# SIM7000_Shield_ES.net
KiCad netlist of a schematic drawn in EAGLE
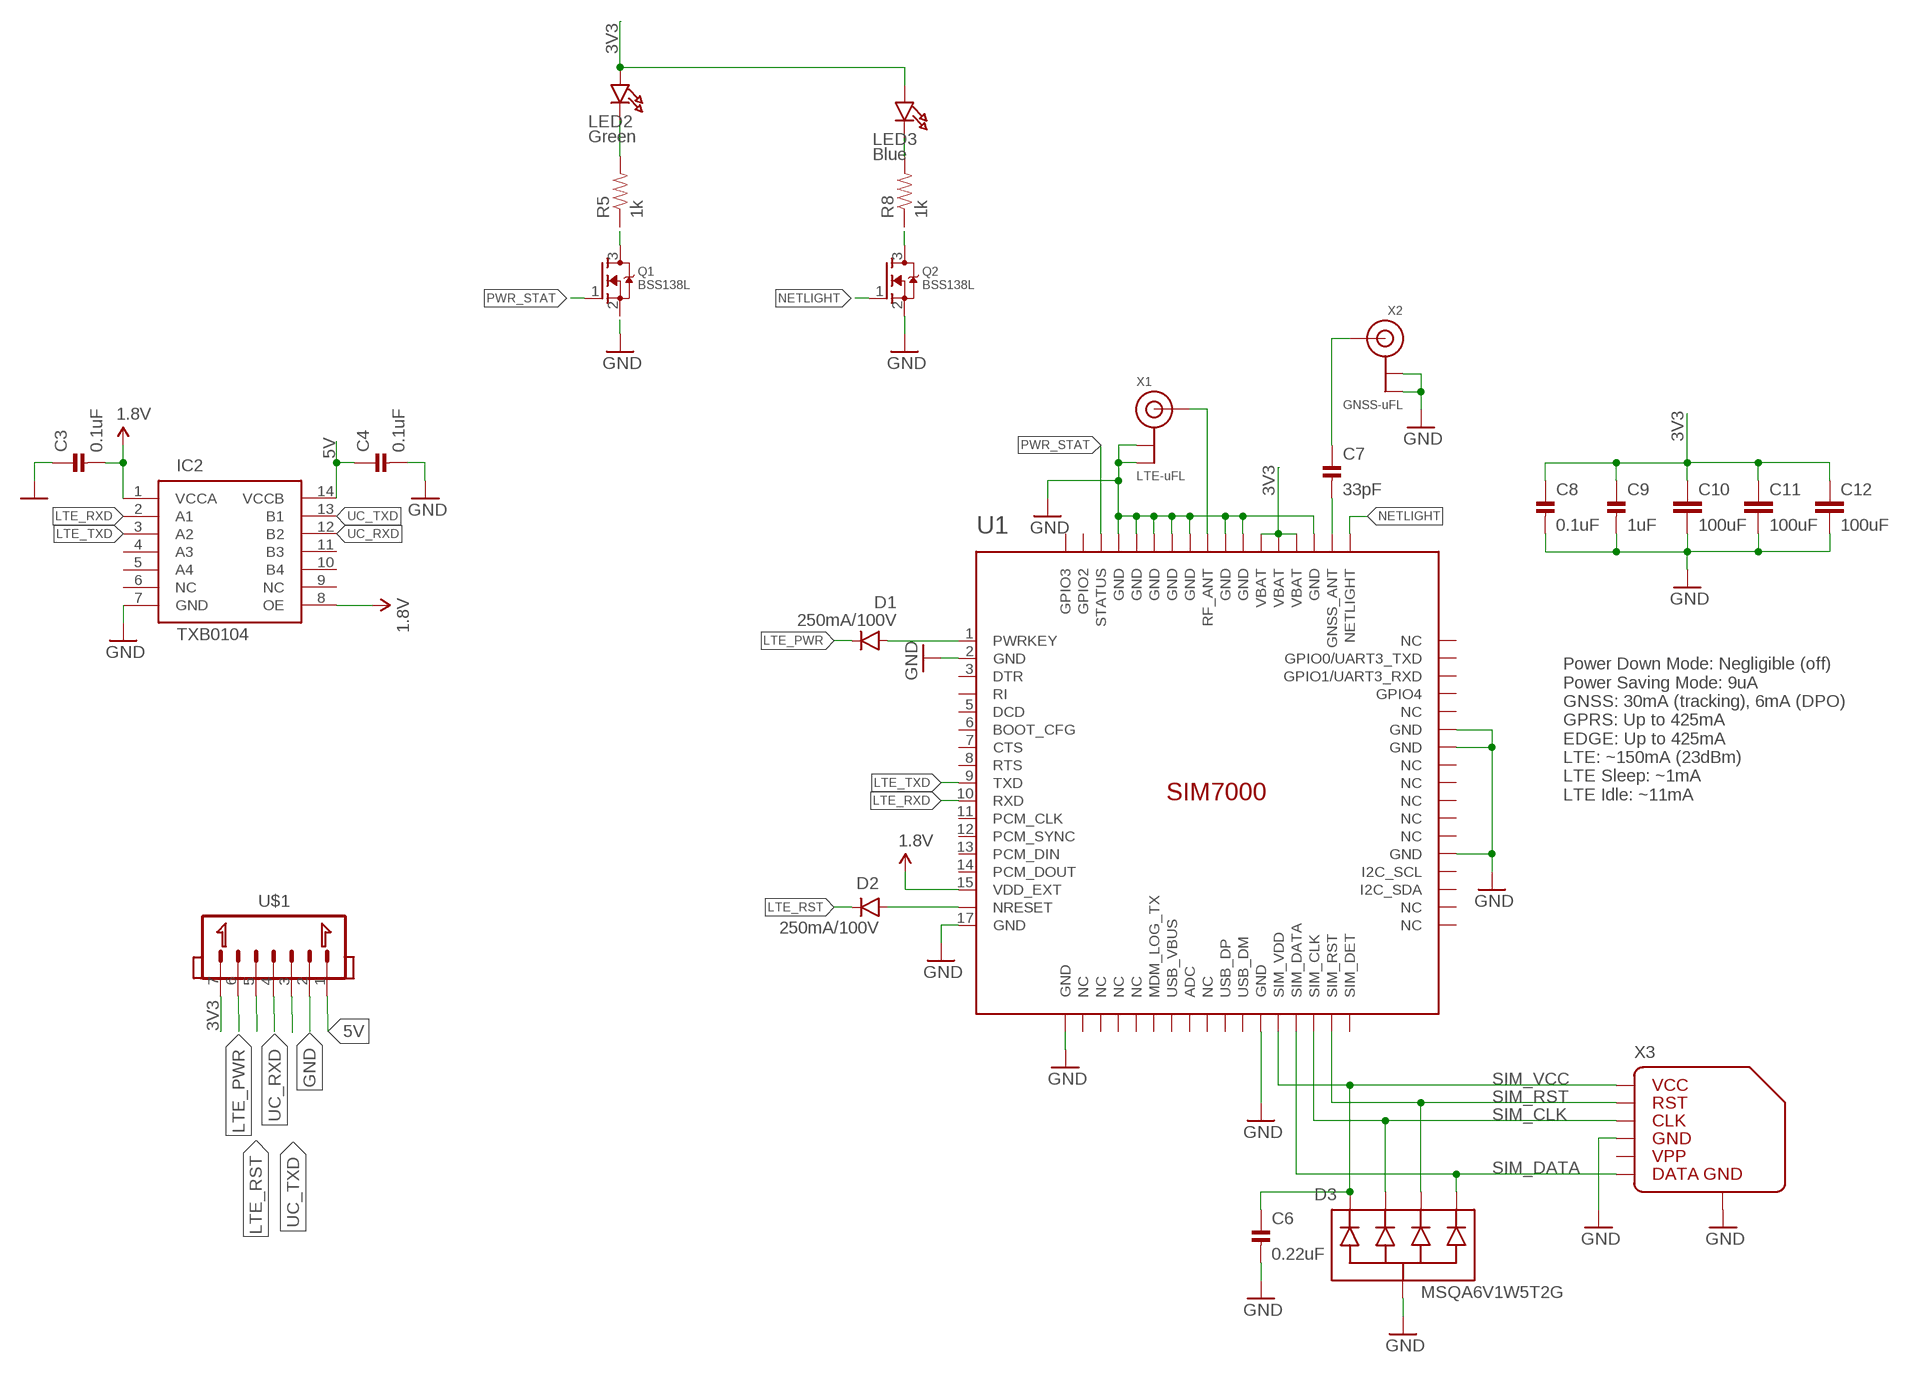
[diagram p0: schematic, sheet 1]

(export (version "E")
  (design (tool "Eeschema 10.0.6"))
  (components
    (comp (ref "C3")
      (value "0.1uF")
      (footprint "eagle-import:CAP_0603")
      (libsource (lib "eagle-import") (part "CAP_CERAMIC_0603"))
    )
    (comp (ref "C4")
      (value "0.1uF")
      (footprint "eagle-import:CAP_0603")
      (libsource (lib "eagle-import") (part "CAP_CERAMIC_0603"))
    )
    (comp (ref "C6")
      (value "0.22uF")
      (footprint "eagle-import:CAP_0603")
      (libsource (lib "eagle-import") (part "CAP_CERAMIC_0603"))
    )
    (comp (ref "C7")
      (value "33pF")
      (footprint "eagle-import:CAP_0603")
      (libsource (lib "eagle-import") (part "CAP_CERAMIC_0603"))
    )
    (comp (ref "C8")
      (value "0.1uF")
      (footprint "eagle-import:CAP_0603")
      (libsource (lib "eagle-import") (part "CAP_CERAMIC_0603"))
    )
    (comp (ref "C9")
      (value "1uF")
      (footprint "eagle-import:CAP_0603")
      (libsource (lib "eagle-import") (part "CAP_CERAMIC_0603"))
    )
    (comp (ref "C10")
      (value "100uF")
      (footprint "eagle-import:1210")
      (libsource (lib "eagle-import") (part "CAPMARKED-1210"))
    )
    (comp (ref "C11")
      (value "100uF")
      (footprint "eagle-import:1210")
      (libsource (lib "eagle-import") (part "CAPMARKED-1210"))
    )
    (comp (ref "C12")
      (value "100uF")
      (footprint "eagle-import:1210")
      (libsource (lib "eagle-import") (part "CAPMARKED-1210"))
    )
    (comp (ref "D1")
      (value "250mA/100V")
      (footprint "eagle-import:SOD-323")
      (libsource (lib "eagle-import") (part "DIODESOD323"))
    )
    (comp (ref "D2")
      (value "250mA/100V")
      (footprint "eagle-import:SOD-323")
      (libsource (lib "eagle-import") (part "DIODESOD323"))
    )
    (comp (ref "D3")
      (value "MSQA6V1W5T2G")
      (footprint "eagle-import:SOT-353")
      (libsource (lib "eagle-import") (part "TVS-DIODE-ARRAY-4X"))
    )
    (comp (ref "IC2")
      (value "TXB0104")
      (footprint "eagle-import:TSSOP-14")
      (libsource (lib "eagle-import") (part "LEVEL_SHIFTER_TXB0104"))
    )
    (comp (ref "LED2")
      (value "Green")
      (footprint "eagle-import:MICROBUILDER_CHIPLED_0603")
      (libsource (lib "eagle-import") (part "LED0603"))
    )
    (comp (ref "LED3")
      (value "Blue")
      (footprint "eagle-import:MICROBUILDER_CHIPLED_0603")
      (libsource (lib "eagle-import") (part "LED0603"))
    )
    (comp (ref "Q1")
      (value "BSS138L")
      (footprint "eagle-import:SOT23-3")
      (libsource (lib "eagle-import") (part "MOSFET-NGENERIC"))
    )
    (comp (ref "Q2")
      (value "BSS138L")
      (footprint "eagle-import:SOT23-3")
      (libsource (lib "eagle-import") (part "MOSFET-NGENERIC"))
    )
    (comp (ref "R5")
      (value "1k")
      (footprint "eagle-import:0603")
      (libsource (lib "eagle-import") (part "RESISTOR0603"))
    )
    (comp (ref "R8")
      (value "1k")
      (footprint "eagle-import:0603")
      (libsource (lib "eagle-import") (part "RESISTOR0603"))
    )
    (comp (ref "U$1")
      (value "JST_1.25_7P")
      (footprint "eagle-import:JST1.25_7P")
      (libsource (lib "eagle-import") (part "JST_1.25_7P"))
    )
    (comp (ref "U1")
      (value "SIM7000")
      (footprint "eagle-import:SIM7000")
      (libsource (lib "eagle-import") (part "SIM7000"))
    )
    (comp (ref "X1")
      (value "LTE-uFL")
      (footprint "eagle-import:U.FL")
      (libsource (lib "eagle-import") (part "ANTENNA_U.FL"))
    )
    (comp (ref "X2")
      (value "GNSS-uFL")
      (footprint "eagle-import:U.FL")
      (libsource (lib "eagle-import") (part "ANTENNA_U.FL"))
    )
    (comp (ref "X3")
      (value "MICROSIM_SOCKET")
      (footprint "eagle-import:MICROSIM_SOCKET")
      (libsource (lib "eagle-import") (part "MICROSIM_SOCKET"))
    )
  )
  (nets
    (net (code "1") (name "/3V3") (class "Default")
      (node (ref "C10") (pin "1") (pinfunction "1_1") (pintype "passive"))
      (node (ref "C11") (pin "1") (pinfunction "1_1") (pintype "passive"))
      (node (ref "C12") (pin "1") (pinfunction "1_1") (pintype "passive"))
      (node (ref "C8") (pin "1") (pinfunction "1_1") (pintype "passive"))
      (node (ref "C9") (pin "1") (pinfunction "1_1") (pintype "passive"))
      (node (ref "LED2") (pin "A") (pinfunction "A_A") (pintype "passive"))
      (node (ref "LED3") (pin "A") (pinfunction "A_A") (pintype "passive"))
      (node (ref "U$1") (pin "7") (pinfunction "7_7") (pintype "passive"))
      (node (ref "U1") (pin "55") (pinfunction "VBAT_55") (pintype "bidirectional"))
      (node (ref "U1") (pin "56") (pinfunction "VBAT_56") (pintype "bidirectional"))
      (node (ref "U1") (pin "57") (pinfunction "VBAT_57") (pintype "bidirectional"))
    )
    (net (code "2") (name "/SIM_CLK") (class "Default")
      (node (ref "D3") (pin "3") (pinfunction "2_3") (pintype "bidirectional"))
      (node (ref "U1") (pin "32") (pinfunction "SIM_CLK_32") (pintype "bidirectional"))
      (node (ref "X3") (pin "C3") (pinfunction "C3_C3") (pintype "passive"))
    )
    (net (code "3") (name "/SIM_DATA") (class "Default")
      (node (ref "D3") (pin "5") (pinfunction "4_5") (pintype "bidirectional"))
      (node (ref "U1") (pin "31") (pinfunction "SIM_DATA_31") (pintype "bidirectional"))
      (node (ref "X3") (pin "C7") (pinfunction "C7_C7") (pintype "passive"))
    )
    (net (code "4") (name "/SIM_RST") (class "Default")
      (node (ref "D3") (pin "4") (pinfunction "3_4") (pintype "bidirectional"))
      (node (ref "U1") (pin "33") (pinfunction "SIM_RST_33") (pintype "bidirectional"))
      (node (ref "X3") (pin "C2") (pinfunction "C2_C2") (pintype "passive"))
    )
    (net (code "5") (name "/SIM_VCC") (class "Default")
      (node (ref "C6") (pin "1") (pinfunction "1_1") (pintype "passive"))
      (node (ref "D3") (pin "1") (pinfunction "1_1") (pintype "bidirectional"))
      (node (ref "U1") (pin "30") (pinfunction "SIM_VDD_30") (pintype "bidirectional"))
      (node (ref "X3") (pin "C1") (pinfunction "C1_C1") (pintype "power_in"))
    )
    (net (code "6") (name "1.8V") (class "Default")
      (node (ref "C3") (pin "2") (pinfunction "2_2") (pintype "passive"))
      (node (ref "IC2") (pin "1") (pinfunction "VCCA_1") (pintype "power_in"))
      (node (ref "IC2") (pin "8") (pinfunction "OE_8") (pintype "bidirectional"))
      (node (ref "U1") (pin "15") (pinfunction "VDD_EXT_15") (pintype "bidirectional"))
    )
    (net (code "7") (name "5V") (class "Default")
      (node (ref "C4") (pin "1") (pinfunction "1_1") (pintype "passive"))
      (node (ref "IC2") (pin "14") (pinfunction "VCCB_14") (pintype "power_in"))
      (node (ref "U$1") (pin "1") (pinfunction "1_1") (pintype "passive"))
    )
    (net (code "8") (name "GND") (class "Default")
      (node (ref "C10") (pin "2") (pinfunction "2_2") (pintype "passive"))
      (node (ref "C11") (pin "2") (pinfunction "2_2") (pintype "passive"))
      (node (ref "C12") (pin "2") (pinfunction "2_2") (pintype "passive"))
      (node (ref "C3") (pin "1") (pinfunction "1_1") (pintype "passive"))
      (node (ref "C4") (pin "2") (pinfunction "2_2") (pintype "passive"))
      (node (ref "C6") (pin "2") (pinfunction "2_2") (pintype "passive"))
      (node (ref "C8") (pin "2") (pinfunction "2_2") (pintype "passive"))
      (node (ref "C9") (pin "2") (pinfunction "2_2") (pintype "passive"))
      (node (ref "D3") (pin "2") (pinfunction "COM_2") (pintype "bidirectional"))
      (node (ref "IC2") (pin "7") (pinfunction "GND_7") (pintype "power_in"))
      (node (ref "Q1") (pin "2") (pinfunction "S_2") (pintype "bidirectional"))
      (node (ref "Q2") (pin "2") (pinfunction "S_2") (pintype "bidirectional"))
      (node (ref "U$1") (pin "2") (pinfunction "2_2") (pintype "passive"))
      (node (ref "U1") (pin "17") (pinfunction "GND_17") (pintype "bidirectional"))
      (node (ref "U1") (pin "18") (pinfunction "GND_18") (pintype "bidirectional"))
      (node (ref "U1") (pin "2") (pinfunction "GND_2") (pintype "bidirectional"))
      (node (ref "U1") (pin "29") (pinfunction "GND_29") (pintype "bidirectional"))
      (node (ref "U1") (pin "39") (pinfunction "GND_39") (pintype "bidirectional"))
      (node (ref "U1") (pin "45") (pinfunction "GND_45") (pintype "bidirectional"))
      (node (ref "U1") (pin "46") (pinfunction "GND_46") (pintype "bidirectional"))
      (node (ref "U1") (pin "54") (pinfunction "GND_54") (pintype "bidirectional"))
      (node (ref "U1") (pin "58") (pinfunction "GND_58") (pintype "bidirectional"))
      (node (ref "U1") (pin "59") (pinfunction "GND_59") (pintype "bidirectional"))
      (node (ref "U1") (pin "61") (pinfunction "GND_61") (pintype "bidirectional"))
      (node (ref "U1") (pin "62") (pinfunction "GND_62") (pintype "bidirectional"))
      (node (ref "U1") (pin "63") (pinfunction "GND_63") (pintype "bidirectional"))
      (node (ref "U1") (pin "64") (pinfunction "GND_64") (pintype "bidirectional"))
      (node (ref "U1") (pin "65") (pinfunction "GND_65") (pintype "bidirectional"))
      (node (ref "X1") (pin "1") (pinfunction "GND_1") (pintype "passive"))
      (node (ref "X1") (pin "2") (pinfunction "GND_2") (pintype "passive"))
      (node (ref "X2") (pin "1") (pinfunction "GND_1") (pintype "passive"))
      (node (ref "X2") (pin "2") (pinfunction "GND_2") (pintype "passive"))
      (node (ref "X3") (pin "C5") (pinfunction "C5_C5") (pintype "power_in"))
      (node (ref "X3") (pin "GND@1") (pinfunction "GND_GND@1") (pintype "power_in"))
      (node (ref "X3") (pin "GND@10") (pinfunction "GND_GND@10") (pintype "power_in"))
      (node (ref "X3") (pin "GND@2") (pinfunction "GND_GND@2") (pintype "power_in"))
      (node (ref "X3") (pin "GND@3") (pinfunction "GND_GND@3") (pintype "power_in"))
      (node (ref "X3") (pin "GND@4") (pinfunction "GND_GND@4") (pintype "power_in"))
      (node (ref "X3") (pin "GND@5") (pinfunction "GND_GND@5") (pintype "power_in"))
      (node (ref "X3") (pin "GND@6") (pinfunction "GND_GND@6") (pintype "power_in"))
      (node (ref "X3") (pin "GND@7") (pinfunction "GND_GND@7") (pintype "power_in"))
      (node (ref "X3") (pin "GND@8") (pinfunction "GND_GND@8") (pintype "power_in"))
      (node (ref "X3") (pin "GND@9") (pinfunction "GND_GND@9") (pintype "power_in"))
    )
    (net (code "9") (name "LTE_PWR") (class "Default")
      (node (ref "D1") (pin "C") (pinfunction "C_C") (pintype "passive"))
      (node (ref "U$1") (pin "6") (pinfunction "6_6") (pintype "passive"))
    )
    (net (code "10") (name "LTE_RST") (class "Default")
      (node (ref "D2") (pin "C") (pinfunction "C_C") (pintype "passive"))
      (node (ref "U$1") (pin "5") (pinfunction "5_5") (pintype "passive"))
    )
    (net (code "11") (name "LTE_RXD") (class "Default")
      (node (ref "IC2") (pin "2") (pinfunction "A1_2") (pintype "bidirectional"))
      (node (ref "U1") (pin "10") (pinfunction "RXD_10") (pintype "bidirectional"))
    )
    (net (code "12") (name "LTE_TXD") (class "Default")
      (node (ref "IC2") (pin "3") (pinfunction "A2_3") (pintype "bidirectional"))
      (node (ref "U1") (pin "9") (pinfunction "TXD_9") (pintype "bidirectional"))
    )
    (net (code "13") (name "NETLIGHT") (class "Default")
      (node (ref "Q2") (pin "1") (pinfunction "G_1") (pintype "bidirectional"))
      (node (ref "U1") (pin "52") (pinfunction "NETLIGHT_52") (pintype "bidirectional"))
    )
    (net (code "14") (name "Net-(LED2-PadC)") (class "Default")
      (node (ref "LED2") (pin "C") (pinfunction "C_C") (pintype "passive"))
      (node (ref "R5") (pin "2") (pinfunction "2_2") (pintype "passive"))
    )
    (net (code "15") (name "Net-(LED3-PadC)") (class "Default")
      (node (ref "LED3") (pin "C") (pinfunction "C_C") (pintype "passive"))
      (node (ref "R8") (pin "2") (pinfunction "2_2") (pintype "passive"))
    )
    (net (code "16") (name "Net-(Q1-D)") (class "Default")
      (node (ref "Q1") (pin "3") (pinfunction "D_3") (pintype "bidirectional"))
      (node (ref "R5") (pin "1") (pinfunction "1_1") (pintype "passive"))
    )
    (net (code "17") (name "Net-(Q2-D)") (class "Default")
      (node (ref "Q2") (pin "3") (pinfunction "D_3") (pintype "bidirectional"))
      (node (ref "R8") (pin "1") (pinfunction "1_1") (pintype "passive"))
    )
    (net (code "18") (name "Net-(U1-GNSS_ANT)") (class "Default")
      (node (ref "C7") (pin "2") (pinfunction "2_2") (pintype "passive"))
      (node (ref "U1") (pin "53") (pinfunction "GNSS_ANT_53") (pintype "bidirectional"))
    )
    (net (code "19") (name "Net-(U1-NRESET)") (class "Default")
      (node (ref "D2") (pin "A") (pinfunction "A_A") (pintype "passive"))
      (node (ref "U1") (pin "16") (pinfunction "NRESET_16") (pintype "bidirectional"))
    )
    (net (code "20") (name "Net-(U1-PWRKEY)") (class "Default")
      (node (ref "D1") (pin "A") (pinfunction "A_A") (pintype "passive"))
      (node (ref "U1") (pin "1") (pinfunction "PWRKEY_1") (pintype "bidirectional"))
    )
    (net (code "21") (name "Net-(U1-RF_ANT)") (class "Default")
      (node (ref "U1") (pin "60") (pinfunction "RF_ANT_60") (pintype "bidirectional"))
      (node (ref "X1") (pin "3") (pinfunction "SIGNAL_3") (pintype "passive"))
    )
    (net (code "22") (name "Net-(X2-SIGNAL)") (class "Default")
      (node (ref "C7") (pin "1") (pinfunction "1_1") (pintype "passive"))
      (node (ref "X2") (pin "3") (pinfunction "SIGNAL_3") (pintype "passive"))
    )
    (net (code "23") (name "PWR_STAT") (class "Default")
      (node (ref "Q1") (pin "1") (pinfunction "G_1") (pintype "bidirectional"))
      (node (ref "U1") (pin "66") (pinfunction "STATUS_66") (pintype "bidirectional"))
    )
    (net (code "24") (name "UC_RXD") (class "Default")
      (node (ref "IC2") (pin "12") (pinfunction "B2_12") (pintype "bidirectional"))
      (node (ref "U$1") (pin "4") (pinfunction "4_4") (pintype "passive"))
    )
    (net (code "25") (name "UC_TXD") (class "Default")
      (node (ref "IC2") (pin "13") (pinfunction "B1_13") (pintype "bidirectional"))
      (node (ref "U$1") (pin "3") (pinfunction "3_3") (pintype "passive"))
    )
    (net (code "26") (name "unconnected-(IC2-A3-Pad4)") (class "Default")
      (node (ref "IC2") (pin "4") (pinfunction "A3_4") (pintype "bidirectional"))
    )
    (net (code "27") (name "unconnected-(IC2-A4-Pad5)") (class "Default")
      (node (ref "IC2") (pin "5") (pinfunction "A4_5") (pintype "bidirectional"))
    )
    (net (code "28") (name "unconnected-(IC2-B3-Pad11)") (class "Default")
      (node (ref "IC2") (pin "11") (pinfunction "B3_11") (pintype "bidirectional"))
    )
    (net (code "29") (name "unconnected-(IC2-B4-Pad10)") (class "Default")
      (node (ref "IC2") (pin "10") (pinfunction "B4_10") (pintype "bidirectional"))
    )
    (net (code "30") (name "unconnected-(IC2-NC-Pad6)") (class "Default")
      (node (ref "IC2") (pin "6") (pinfunction "NC_6") (pintype "bidirectional"))
    )
    (net (code "31") (name "unconnected-(IC2-NC-Pad9)") (class "Default")
      (node (ref "IC2") (pin "9") (pinfunction "NC_9") (pintype "bidirectional"))
    )
    (net (code "32") (name "unconnected-(U1-ADC-Pad25)") (class "Default")
      (node (ref "U1") (pin "25") (pinfunction "ADC_25") (pintype "bidirectional"))
    )
    (net (code "33") (name "unconnected-(U1-BOOT_CFG-Pad6)") (class "Default")
      (node (ref "U1") (pin "6") (pinfunction "BOOT_CFG_6") (pintype "bidirectional"))
    )
    (net (code "34") (name "unconnected-(U1-CTS-Pad7)") (class "Default")
      (node (ref "U1") (pin "7") (pinfunction "CTS_7") (pintype "bidirectional"))
    )
    (net (code "35") (name "unconnected-(U1-DCD-Pad5)") (class "Default")
      (node (ref "U1") (pin "5") (pinfunction "DCD_5") (pintype "bidirectional"))
    )
    (net (code "36") (name "unconnected-(U1-DTR-Pad3)") (class "Default")
      (node (ref "U1") (pin "3") (pinfunction "DTR_3") (pintype "bidirectional"))
    )
    (net (code "37") (name "unconnected-(U1-GPIO0{slash}UART3_TXD-Pad50)") (class "Default")
      (node (ref "U1") (pin "50") (pinfunction "GPIO0/UART3_TXD_50") (pintype "bidirectional"))
    )
    (net (code "38") (name "unconnected-(U1-GPIO1{slash}UART3_RXD-Pad49)") (class "Default")
      (node (ref "U1") (pin "49") (pinfunction "GPIO1/UART3_RXD_49") (pintype "bidirectional"))
    )
    (net (code "39") (name "unconnected-(U1-GPIO2-Pad67)") (class "Default")
      (node (ref "U1") (pin "67") (pinfunction "GPIO2_67") (pintype "bidirectional"))
    )
    (net (code "40") (name "unconnected-(U1-GPIO3-Pad68)") (class "Default")
      (node (ref "U1") (pin "68") (pinfunction "GPIO3_68") (pintype "bidirectional"))
    )
    (net (code "41") (name "unconnected-(U1-GPIO4-Pad48)") (class "Default")
      (node (ref "U1") (pin "48") (pinfunction "GPIO4_48") (pintype "bidirectional"))
    )
    (net (code "42") (name "unconnected-(U1-I2C_SCL-Pad38)") (class "Default")
      (node (ref "U1") (pin "38") (pinfunction "I2C_SCL_38") (pintype "bidirectional"))
    )
    (net (code "43") (name "unconnected-(U1-I2C_SDA-Pad37)") (class "Default")
      (node (ref "U1") (pin "37") (pinfunction "I2C_SDA_37") (pintype "bidirectional"))
    )
    (net (code "44") (name "unconnected-(U1-MDM_LOG_TX-Pad23)") (class "Default")
      (node (ref "U1") (pin "23") (pinfunction "MDM_LOG_TX_23") (pintype "bidirectional"))
    )
    (net (code "45") (name "unconnected-(U1-NC-Pad19)") (class "Default")
      (node (ref "U1") (pin "19") (pinfunction "NC_19") (pintype "bidirectional"))
    )
    (net (code "46") (name "unconnected-(U1-NC-Pad20)") (class "Default")
      (node (ref "U1") (pin "20") (pinfunction "NC_20") (pintype "bidirectional"))
    )
    (net (code "47") (name "unconnected-(U1-NC-Pad21)") (class "Default")
      (node (ref "U1") (pin "21") (pinfunction "NC_21") (pintype "bidirectional"))
    )
    (net (code "48") (name "unconnected-(U1-NC-Pad22)") (class "Default")
      (node (ref "U1") (pin "22") (pinfunction "NC_22") (pintype "bidirectional"))
    )
    (net (code "49") (name "unconnected-(U1-NC-Pad26)") (class "Default")
      (node (ref "U1") (pin "26") (pinfunction "NC_26") (pintype "bidirectional"))
    )
    (net (code "50") (name "unconnected-(U1-NC-Pad35)") (class "Default")
      (node (ref "U1") (pin "35") (pinfunction "NC_35") (pintype "bidirectional"))
    )
    (net (code "51") (name "unconnected-(U1-NC-Pad36)") (class "Default")
      (node (ref "U1") (pin "36") (pinfunction "NC_36") (pintype "bidirectional"))
    )
    (net (code "52") (name "unconnected-(U1-NC-Pad40)") (class "Default")
      (node (ref "U1") (pin "40") (pinfunction "NC_40") (pintype "bidirectional"))
    )
    (net (code "53") (name "unconnected-(U1-NC-Pad41)") (class "Default")
      (node (ref "U1") (pin "41") (pinfunction "NC_41") (pintype "bidirectional"))
    )
    (net (code "54") (name "unconnected-(U1-NC-Pad42)") (class "Default")
      (node (ref "U1") (pin "42") (pinfunction "NC_42") (pintype "bidirectional"))
    )
    (net (code "55") (name "unconnected-(U1-NC-Pad43)") (class "Default")
      (node (ref "U1") (pin "43") (pinfunction "NC_43") (pintype "bidirectional"))
    )
    (net (code "56") (name "unconnected-(U1-NC-Pad44)") (class "Default")
      (node (ref "U1") (pin "44") (pinfunction "NC_44") (pintype "bidirectional"))
    )
    (net (code "57") (name "unconnected-(U1-NC-Pad47)") (class "Default")
      (node (ref "U1") (pin "47") (pinfunction "NC_47") (pintype "bidirectional"))
    )
    (net (code "58") (name "unconnected-(U1-NC-Pad51)") (class "Default")
      (node (ref "U1") (pin "51") (pinfunction "NC_51") (pintype "bidirectional"))
    )
    (net (code "59") (name "unconnected-(U1-PCM_CLK-Pad11)") (class "Default")
      (node (ref "U1") (pin "11") (pinfunction "PCM_CLK_11") (pintype "bidirectional"))
    )
    (net (code "60") (name "unconnected-(U1-PCM_DIN-Pad13)") (class "Default")
      (node (ref "U1") (pin "13") (pinfunction "PCM_DIN_13") (pintype "bidirectional"))
    )
    (net (code "61") (name "unconnected-(U1-PCM_DOUT-Pad14)") (class "Default")
      (node (ref "U1") (pin "14") (pinfunction "PCM_DOUT_14") (pintype "bidirectional"))
    )
    (net (code "62") (name "unconnected-(U1-PCM_SYNC-Pad12)") (class "Default")
      (node (ref "U1") (pin "12") (pinfunction "PCM_SYNC_12") (pintype "bidirectional"))
    )
    (net (code "63") (name "unconnected-(U1-RI-Pad4)") (class "Default")
      (node (ref "U1") (pin "4") (pinfunction "RI_4") (pintype "bidirectional"))
    )
    (net (code "64") (name "unconnected-(U1-RTS-Pad8)") (class "Default")
      (node (ref "U1") (pin "8") (pinfunction "RTS_8") (pintype "bidirectional"))
    )
    (net (code "65") (name "unconnected-(U1-SIM_DET-Pad34)") (class "Default")
      (node (ref "U1") (pin "34") (pinfunction "SIM_DET_34") (pintype "bidirectional"))
    )
    (net (code "66") (name "unconnected-(U1-USB_DM-Pad28)") (class "Default")
      (node (ref "U1") (pin "28") (pinfunction "USB_DM_28") (pintype "bidirectional"))
    )
    (net (code "67") (name "unconnected-(U1-USB_DP-Pad27)") (class "Default")
      (node (ref "U1") (pin "27") (pinfunction "USB_DP_27") (pintype "bidirectional"))
    )
    (net (code "68") (name "unconnected-(U1-USB_VBUS-Pad24)") (class "Default")
      (node (ref "U1") (pin "24") (pinfunction "USB_VBUS_24") (pintype "bidirectional"))
    )
    (net (code "69") (name "unconnected-(X3-PadC6)") (class "Default")
      (node (ref "X3") (pin "C6") (pinfunction "C6_C6") (pintype "passive"))
    )
  )
)
